# TEST_PCB.net
KiCad netlist of a schematic drawn in EAGLE
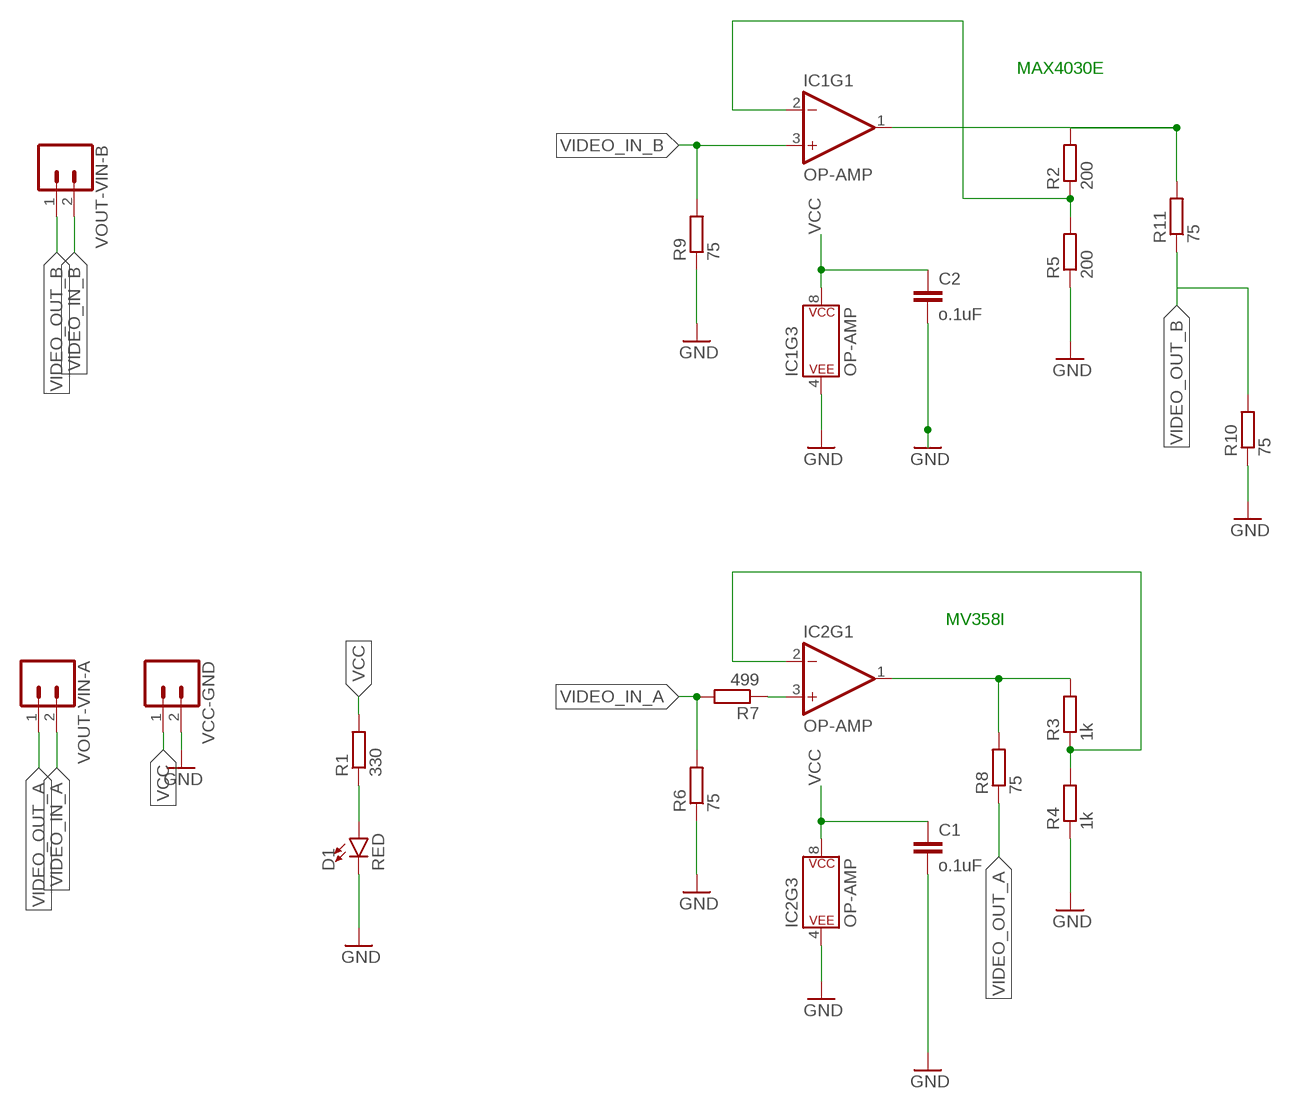
[diagram p0: schematic, sheet 1]

(export (version "E")
  (design (tool "Eeschema 10.0.6"))
  (components
    (comp (ref "C1")
      (value "o.1uF")
      (footprint "eagle-import:C0603K")
      (libsource (lib "eagle-import") (part "C-EUC0603K"))
    )
    (comp (ref "C2")
      (value "o.1uF")
      (footprint "eagle-import:C0603K")
      (libsource (lib "eagle-import") (part "C-EUC0603K"))
    )
    (comp (ref "D1")
      (value "RED")
      (footprint "eagle-import:LED-1206")
      (libsource (lib "eagle-import") (part "LED-RED1206"))
    )
    (comp (ref "IC1")
      (value "OP-AMP")
      (footprint "eagle-import:SO08")
      (libsource (lib "eagle-import") (part "OPAMP-DUALU"))
    )
    (comp (ref "IC2")
      (value "OP-AMP")
      (footprint "eagle-import:SO08")
      (libsource (lib "eagle-import") (part "OPAMP-DUALU"))
    )
    (comp (ref "R1")
      (value "330")
      (footprint "eagle-import:R0603")
      (libsource (lib "eagle-import") (part "R-EU_R0603"))
    )
    (comp (ref "R2")
      (value "200")
      (footprint "eagle-import:R0603")
      (libsource (lib "eagle-import") (part "R-EU_R0603"))
    )
    (comp (ref "R3")
      (value "1k")
      (footprint "eagle-import:R0603")
      (libsource (lib "eagle-import") (part "R-EU_R0603"))
    )
    (comp (ref "R4")
      (value "1k")
      (footprint "eagle-import:R0603")
      (libsource (lib "eagle-import") (part "R-EU_R0603"))
    )
    (comp (ref "R5")
      (value "200")
      (footprint "eagle-import:R0603")
      (libsource (lib "eagle-import") (part "R-EU_R0603"))
    )
    (comp (ref "R6")
      (value "75")
      (footprint "eagle-import:R0603")
      (libsource (lib "eagle-import") (part "R-EU_R0603"))
    )
    (comp (ref "R7")
      (value "499")
      (footprint "eagle-import:R0603")
      (libsource (lib "eagle-import") (part "R-EU_R0603"))
    )
    (comp (ref "R8")
      (value "75")
      (footprint "eagle-import:R0603")
      (libsource (lib "eagle-import") (part "R-EU_R0603"))
    )
    (comp (ref "R9")
      (value "75")
      (footprint "eagle-import:R0603")
      (libsource (lib "eagle-import") (part "R-EU_R0603"))
    )
    (comp (ref "R10")
      (value "75")
      (footprint "eagle-import:R0603")
      (libsource (lib "eagle-import") (part "R-EU_R0603"))
    )
    (comp (ref "R11")
      (value "75")
      (footprint "eagle-import:R0603")
      (libsource (lib "eagle-import") (part "R-EU_R0603"))
    )
    (comp (ref "VCC-GND")
      (value "CONN_02")
      (footprint "eagle-import:1X02")
      (libsource (lib "eagle-import") (part "CONN_02"))
    )
    (comp (ref "VOUT-VIN-A")
      (value "CONN_02")
      (footprint "eagle-import:1X02")
      (libsource (lib "eagle-import") (part "CONN_02"))
    )
    (comp (ref "VOUT-VIN-B")
      (value "CONN_02")
      (footprint "eagle-import:1X02")
      (libsource (lib "eagle-import") (part "CONN_02"))
    )
  )
  (nets
    (net (code "1") (name "GND") (class "Default")
      (node (ref "C1") (pin "2") (pinfunction "2_2") (pintype "passive"))
      (node (ref "C2") (pin "2") (pinfunction "2_2") (pintype "passive"))
      (node (ref "D1") (pin "C") (pinfunction "C_C") (pintype "passive"))
      (node (ref "IC1") (pin "4") (pinfunction "P$V-_4") (pintype "bidirectional"))
      (node (ref "IC2") (pin "4") (pinfunction "P$V-_4") (pintype "bidirectional"))
      (node (ref "R10") (pin "1") (pinfunction "1_1") (pintype "passive"))
      (node (ref "R4") (pin "1") (pinfunction "1_1") (pintype "passive"))
      (node (ref "R5") (pin "1") (pinfunction "1_1") (pintype "passive"))
      (node (ref "R6") (pin "1") (pinfunction "1_1") (pintype "passive"))
      (node (ref "R9") (pin "1") (pinfunction "1_1") (pintype "passive"))
      (node (ref "VCC-GND") (pin "2") (pinfunction "2_2") (pintype "passive"))
    )
    (net (code "2") (name "Net-(D1-PadA)") (class "Default")
      (node (ref "D1") (pin "A") (pinfunction "A_A") (pintype "passive"))
      (node (ref "R1") (pin "1") (pinfunction "1_1") (pintype "passive"))
    )
    (net (code "3") (name "Net-(IC1A--IN)") (class "Default")
      (node (ref "IC1") (pin "2") (pinfunction "-IN_2") (pintype "input"))
      (node (ref "R2") (pin "1") (pinfunction "1_1") (pintype "passive"))
      (node (ref "R5") (pin "2") (pinfunction "2_2") (pintype "passive"))
    )
    (net (code "4") (name "Net-(IC1A-OUT)") (class "Default")
      (node (ref "IC1") (pin "1") (pinfunction "OUT_1") (pintype "output"))
      (node (ref "R11") (pin "2") (pinfunction "2_2") (pintype "passive"))
      (node (ref "R2") (pin "2") (pinfunction "2_2") (pintype "passive"))
    )
    (net (code "5") (name "Net-(IC2A-+IN)") (class "Default")
      (node (ref "IC2") (pin "3") (pinfunction "+IN_3") (pintype "input"))
      (node (ref "R7") (pin "1") (pinfunction "1_1") (pintype "passive"))
    )
    (net (code "6") (name "Net-(IC2A--IN)") (class "Default")
      (node (ref "IC2") (pin "2") (pinfunction "-IN_2") (pintype "input"))
      (node (ref "R3") (pin "1") (pinfunction "1_1") (pintype "passive"))
      (node (ref "R4") (pin "2") (pinfunction "2_2") (pintype "passive"))
    )
    (net (code "7") (name "Net-(IC2A-OUT)") (class "Default")
      (node (ref "IC2") (pin "1") (pinfunction "OUT_1") (pintype "output"))
      (node (ref "R3") (pin "2") (pinfunction "2_2") (pintype "passive"))
      (node (ref "R8") (pin "2") (pinfunction "2_2") (pintype "passive"))
    )
    (net (code "8") (name "VCC") (class "Default")
      (node (ref "C1") (pin "1") (pinfunction "1_1") (pintype "passive"))
      (node (ref "C2") (pin "1") (pinfunction "1_1") (pintype "passive"))
      (node (ref "IC1") (pin "8") (pinfunction "P$V+_8") (pintype "bidirectional"))
      (node (ref "IC2") (pin "8") (pinfunction "P$V+_8") (pintype "bidirectional"))
      (node (ref "R1") (pin "2") (pinfunction "2_2") (pintype "passive"))
      (node (ref "VCC-GND") (pin "1") (pinfunction "1_1") (pintype "passive"))
    )
    (net (code "9") (name "VIDEO_IN_A") (class "Default")
      (node (ref "R6") (pin "2") (pinfunction "2_2") (pintype "passive"))
      (node (ref "R7") (pin "2") (pinfunction "2_2") (pintype "passive"))
      (node (ref "VOUT-VIN-A") (pin "2") (pinfunction "2_2") (pintype "passive"))
    )
    (net (code "10") (name "VIDEO_IN_B") (class "Default")
      (node (ref "IC1") (pin "3") (pinfunction "+IN_3") (pintype "input"))
      (node (ref "R9") (pin "2") (pinfunction "2_2") (pintype "passive"))
      (node (ref "VOUT-VIN-B") (pin "2") (pinfunction "2_2") (pintype "passive"))
    )
    (net (code "11") (name "VIDEO_OUT_A") (class "Default")
      (node (ref "R8") (pin "1") (pinfunction "1_1") (pintype "passive"))
      (node (ref "VOUT-VIN-A") (pin "1") (pinfunction "1_1") (pintype "passive"))
    )
    (net (code "12") (name "VIDEO_OUT_B") (class "Default")
      (node (ref "R10") (pin "2") (pinfunction "2_2") (pintype "passive"))
      (node (ref "R11") (pin "1") (pinfunction "1_1") (pintype "passive"))
      (node (ref "VOUT-VIN-B") (pin "1") (pinfunction "1_1") (pintype "passive"))
    )
  )
)
